# Touch_Sensors.net
KiCad netlist of a schematic drawn in Altium Designer
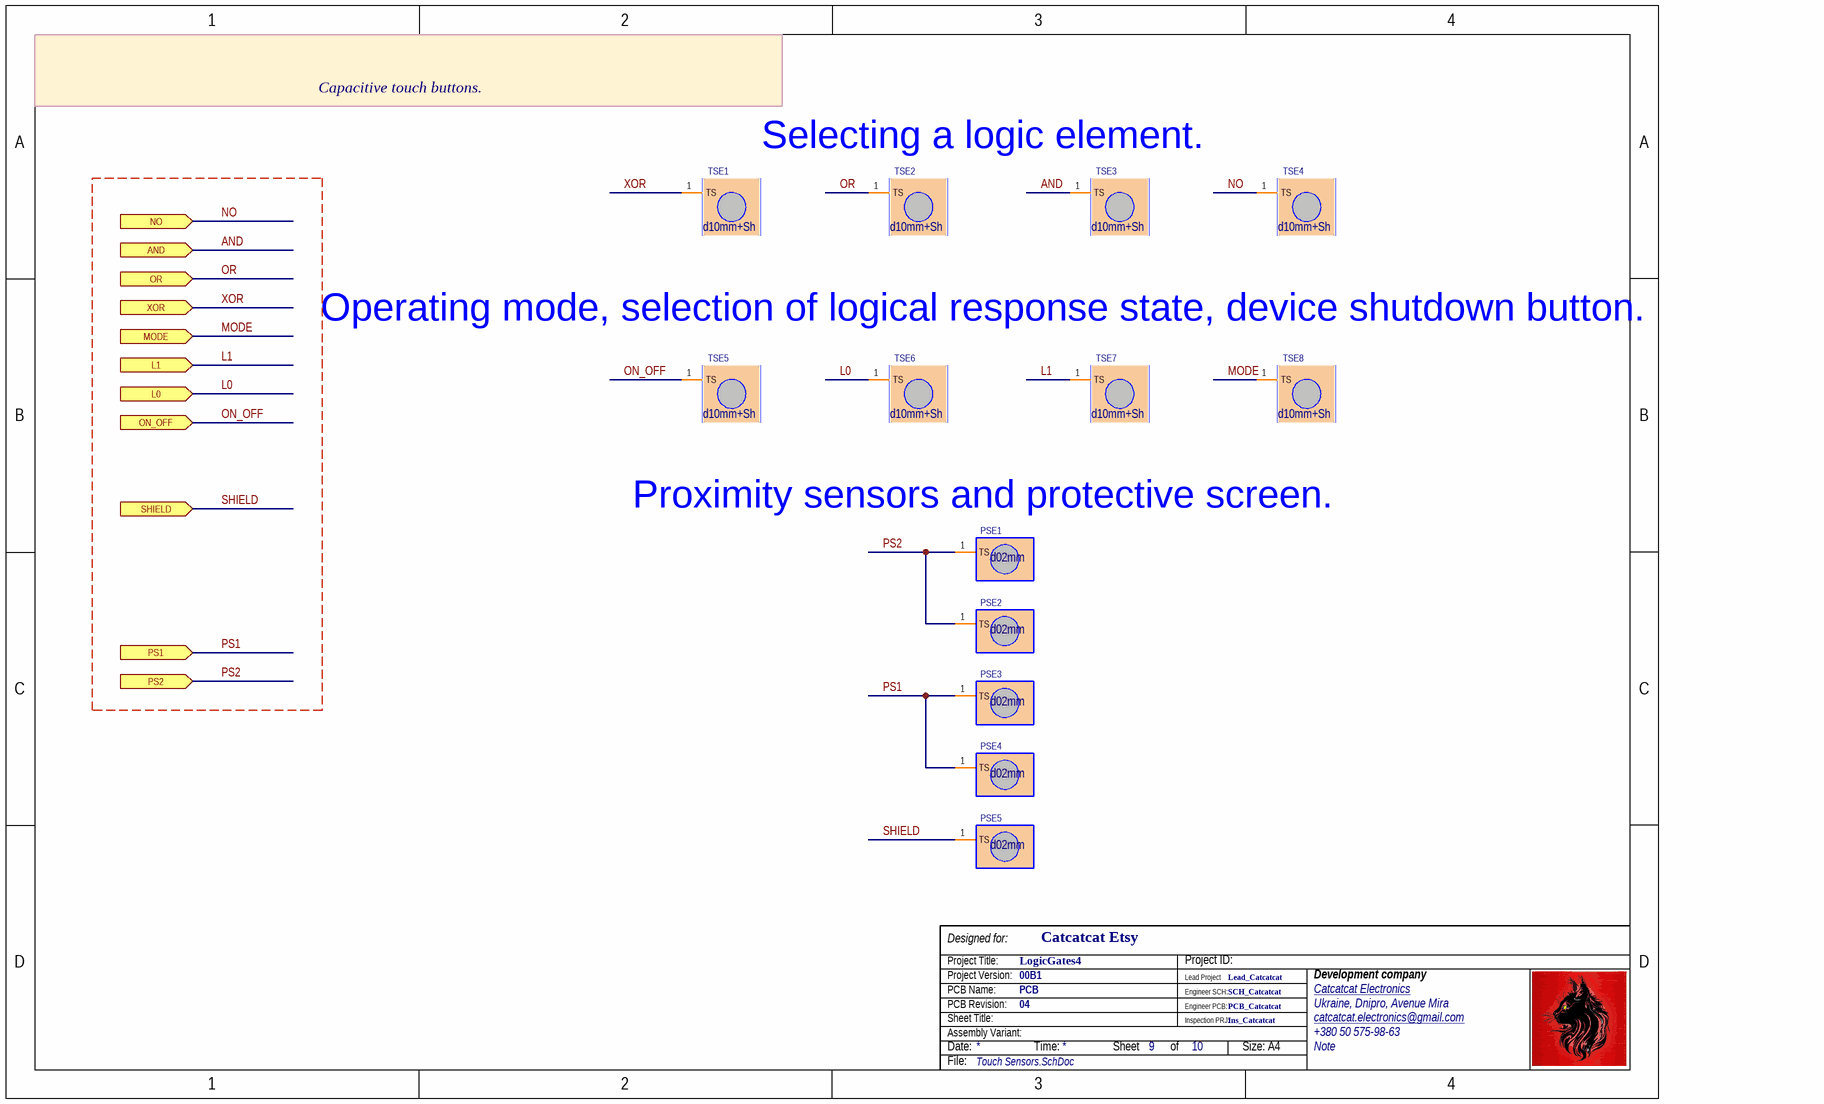
[diagram p0: Touch Sensors.SchDoc]

(export (version "E")
  (design (tool "Eeschema 10.0.6"))
  (components
    (comp (ref "PSE1")
      (value "Connection point")
      (footprint "Connection point")
      (description "Proximity sensor,")
      (fields (field (name "PUBLISHER") "Catcatcat Electronics"))
      (libsource (lib "Discret") (part "Connection point"))
    )
    (comp (ref "PSE2")
      (value "Connection point")
      (footprint "Connection point")
      (description "Proximity sensor,")
      (fields (field (name "PUBLISHER") "Catcatcat Electronics"))
      (libsource (lib "Discret") (part "Connection point"))
    )
    (comp (ref "PSE3")
      (value "Connection point")
      (footprint "Connection point")
      (description "Proximity sensor,")
      (fields (field (name "PUBLISHER") "Catcatcat Electronics"))
      (libsource (lib "Discret") (part "Connection point"))
    )
    (comp (ref "PSE4")
      (value "Connection point")
      (footprint "Connection point")
      (description "Proximity sensor,")
      (fields (field (name "PUBLISHER") "Catcatcat Electronics"))
      (libsource (lib "Discret") (part "Connection point"))
    )
    (comp (ref "PSE5")
      (value "Connection point")
      (footprint "Connection point")
      (description "Proximity sensor,")
      (fields (field (name "PUBLISHER") "Catcatcat Electronics"))
      (libsource (lib "Discret") (part "Connection point"))
    )
    (comp (ref "TSE1")
      (value "Touch Sensors d10mm_Z")
      (footprint "Circle d10mm_NOV1")
      (description "Touch Sensors,")
      (fields (field (name "PUBLISHER") "Catcatcat Electronics"))
      (libsource (lib "Discret") (part "Touch Sensors d10mm_Z"))
    )
    (comp (ref "TSE2")
      (value "Touch Sensors d10mm_Z")
      (footprint "Circle d10mm_NOV1")
      (description "Touch Sensors,")
      (fields (field (name "PUBLISHER") "Catcatcat Electronics"))
      (libsource (lib "Discret") (part "Touch Sensors d10mm_Z"))
    )
    (comp (ref "TSE3")
      (value "Touch Sensors d10mm_Z")
      (footprint "Circle d10mm_NOV1")
      (description "Touch Sensors,")
      (fields (field (name "PUBLISHER") "Catcatcat Electronics"))
      (libsource (lib "Discret") (part "Touch Sensors d10mm_Z"))
    )
    (comp (ref "TSE4")
      (value "Touch Sensors d10mm_Z")
      (footprint "Circle d10mm_NOV1")
      (description "Touch Sensors,")
      (fields (field (name "PUBLISHER") "Catcatcat Electronics"))
      (libsource (lib "Discret") (part "Touch Sensors d10mm_Z"))
    )
    (comp (ref "TSE5")
      (value "Touch Sensors d10mm_Z")
      (footprint "Circle d10mm_NOV1")
      (description "Touch Sensors,")
      (fields (field (name "PUBLISHER") "Catcatcat Electronics"))
      (libsource (lib "Discret") (part "Touch Sensors d10mm_Z"))
    )
    (comp (ref "TSE6")
      (value "Touch Sensors d10mm_Z")
      (footprint "Circle d10mm_NOV1")
      (description "Touch Sensors,")
      (fields (field (name "PUBLISHER") "Catcatcat Electronics"))
      (libsource (lib "Discret") (part "Touch Sensors d10mm_Z"))
    )
    (comp (ref "TSE7")
      (value "Touch Sensors d10mm_Z")
      (footprint "Circle d10mm_NOV1")
      (description "Touch Sensors,")
      (fields (field (name "PUBLISHER") "Catcatcat Electronics"))
      (libsource (lib "Discret") (part "Touch Sensors d10mm_Z"))
    )
    (comp (ref "TSE8")
      (value "Touch Sensors d10mm_Z")
      (footprint "Circle d10mm_NOV1")
      (description "Touch Sensors,")
      (fields (field (name "PUBLISHER") "Catcatcat Electronics"))
      (libsource (lib "Discret") (part "Touch Sensors d10mm_Z"))
    )
  )
  (nets
    (net (code "1") (name "/AND") (class "Default")
      (node (ref "TSE3") (pin "1") (pinfunction "TS_1") (pintype "passive"))
    )
    (net (code "2") (name "/L0") (class "Default")
      (node (ref "TSE6") (pin "1") (pinfunction "TS_1") (pintype "passive"))
    )
    (net (code "3") (name "/L1") (class "Default")
      (node (ref "TSE7") (pin "1") (pinfunction "TS_1") (pintype "passive"))
    )
    (net (code "4") (name "/MODE") (class "Default")
      (node (ref "TSE8") (pin "1") (pinfunction "TS_1") (pintype "passive"))
    )
    (net (code "5") (name "/NO") (class "Default")
      (node (ref "TSE4") (pin "1") (pinfunction "TS_1") (pintype "passive"))
    )
    (net (code "6") (name "/ON_OFF") (class "Default")
      (node (ref "TSE5") (pin "1") (pinfunction "TS_1") (pintype "passive"))
    )
    (net (code "7") (name "/OR") (class "Default")
      (node (ref "TSE2") (pin "1") (pinfunction "TS_1") (pintype "passive"))
    )
    (net (code "8") (name "/PS1") (class "Default")
      (node (ref "PSE3") (pin "1") (pinfunction "TS_1") (pintype "passive"))
      (node (ref "PSE4") (pin "1") (pinfunction "TS_1") (pintype "passive"))
    )
    (net (code "9") (name "/PS2") (class "Default")
      (node (ref "PSE1") (pin "1") (pinfunction "TS_1") (pintype "passive"))
      (node (ref "PSE2") (pin "1") (pinfunction "TS_1") (pintype "passive"))
    )
    (net (code "10") (name "/SHIELD") (class "Default")
      (node (ref "PSE5") (pin "1") (pinfunction "TS_1") (pintype "passive"))
    )
    (net (code "11") (name "/XOR") (class "Default")
      (node (ref "TSE1") (pin "1") (pinfunction "TS_1") (pintype "passive"))
    )
  )
)
